# 05.net
KiCad netlist of a schematic drawn in Altium Designer
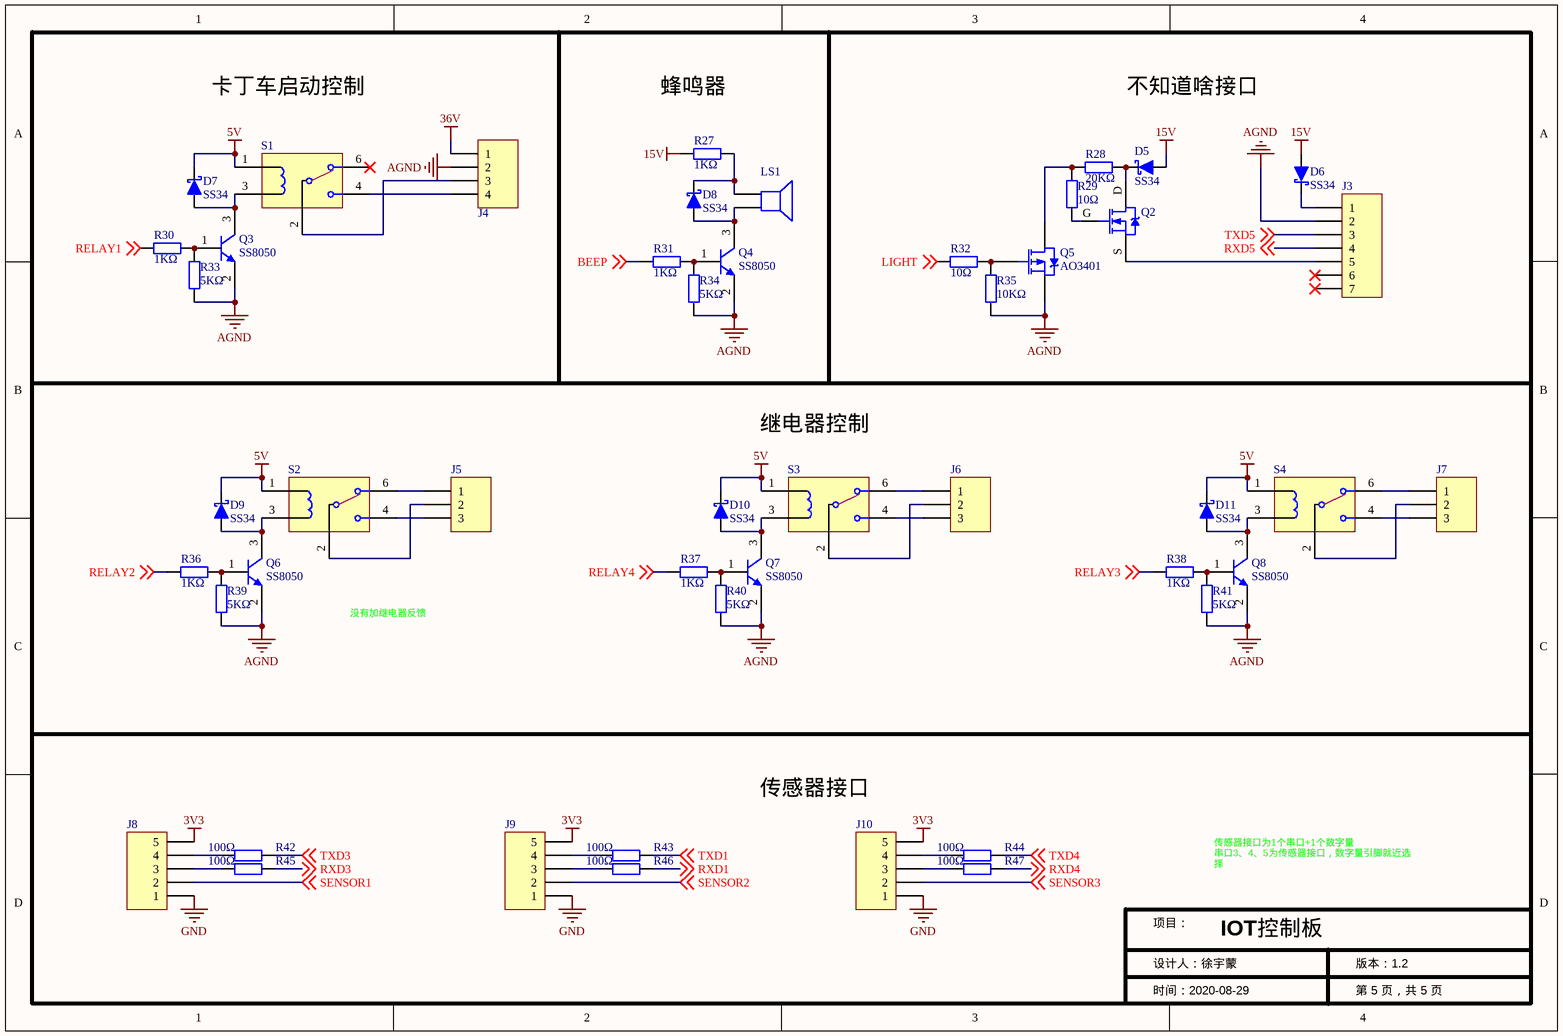
[diagram p0: 05_外部接口与其他部分.SchDoc]

(export (version "E")
  (design (tool "Eeschema 10.0.6"))
  (components
    (comp (ref "D5")
      (value "SS34")
      (footprint "SMA(DO-214AC)")
      (description "Schottky Diode")
      (fields (field (name "PUBLISHER") "Altium Limited"))
      (libsource (lib "元件库") (part "D Schottky"))
    )
    (comp (ref "D6")
      (value "SS34")
      (footprint "SMA(DO-214AC)")
      (description "Schottky Diode")
      (fields (field (name "PUBLISHER") "Altium Limited"))
      (libsource (lib "元件库") (part "D Schottky"))
    )
    (comp (ref "D7")
      (value "SS34")
      (footprint "SMA(DO-214AC)")
      (description "Schottky Diode")
      (fields (field (name "PUBLISHER") "Altium Limited"))
      (libsource (lib "元件库") (part "D Schottky"))
    )
    (comp (ref "D8")
      (value "SS34")
      (footprint "SMA(DO-214AC)")
      (description "Schottky Diode")
      (fields (field (name "PUBLISHER") "Altium Limited"))
      (libsource (lib "元件库") (part "D Schottky"))
    )
    (comp (ref "D9")
      (value "SS34")
      (footprint "SMA(DO-214AC)")
      (description "Schottky Diode")
      (fields (field (name "PUBLISHER") "Altium Limited"))
      (libsource (lib "元件库") (part "D Schottky"))
    )
    (comp (ref "D10")
      (value "SS34")
      (footprint "SMA(DO-214AC)")
      (description "Schottky Diode")
      (fields (field (name "PUBLISHER") "Altium Limited"))
      (libsource (lib "元件库") (part "D Schottky"))
    )
    (comp (ref "D11")
      (value "SS34")
      (footprint "SMA(DO-214AC)")
      (description "Schottky Diode")
      (fields (field (name "PUBLISHER") "Altium Limited"))
      (libsource (lib "元件库") (part "D Schottky"))
    )
    (comp (ref "J3")
      (value "Header7")
      (footprint "Header_7X1_XH_2.54_弯针")
      (description "接插件")
      (libsource (lib "Arrowy_Racing") (part "Header7"))
    )
    (comp (ref "J4")
      (value "Header 4")
      (footprint "Header_4P_XH_2.54_弯脚")
      (description "接插件")
      (fields (field (name "PUBLISHER") "Altium Limited"))
      (libsource (lib "Arrowy_Racing") (part "Header 4"))
    )
    (comp (ref "J5")
      (value "Header3")
      (footprint "Header_3X1_XH_2.54_弯脚")
      (description "接插件")
      (libsource (lib "Arrowy_Racing") (part "Header3"))
    )
    (comp (ref "J6")
      (value "Header3")
      (footprint "Header_3X1_XH_2.54_弯脚")
      (description "接插件")
      (libsource (lib "Arrowy_Racing") (part "Header3"))
    )
    (comp (ref "J7")
      (value "Header3")
      (footprint "Header_3X1_XH_2.54_弯脚")
      (description "接插件")
      (libsource (lib "Arrowy_Racing") (part "Header3"))
    )
    (comp (ref "J8")
      (value "Header5")
      (footprint "Header_5X1_XH_2.54_弯针")
      (description "接插件")
      (libsource (lib "Arrowy_Racing") (part "Header5"))
    )
    (comp (ref "J9")
      (value "Header5")
      (footprint "Header_5X1_XH_2.54_弯针")
      (description "接插件")
      (libsource (lib "Arrowy_Racing") (part "Header5"))
    )
    (comp (ref "J10")
      (value "Header5")
      (footprint "Header_5X1_XH_2.54_弯针")
      (description "接插件")
      (libsource (lib "Arrowy_Racing") (part "Header5"))
    )
    (comp (ref "LS1")
      (value "蜂鸣器")
      (footprint "蜂鸣器 9*5mm")
      (description "Loudspeaker")
      (fields (field (name "PUBLISHER") "Altium Limited"))
      (libsource (lib "Arrowy_Racing") (part "Speaker"))
    )
    (comp (ref "Q2")
      (value "AO3400")
      (footprint "SOT-23-MOSFET")
      (description "N沟道MOS管")
      (libsource (lib "Arrowy_Racing") (part "MOSFET-N"))
    )
    (comp (ref "Q3")
      (value "SS8050")
      (footprint "SOT-23")
      (description "NPN贴片三极管")
      (fields (field (name "PUBLISHER") "Altium Limited"))
      (libsource (lib "Arrowy_Racing") (part "SS8050"))
    )
    (comp (ref "Q4")
      (value "SS8050")
      (footprint "SOT-23")
      (description "NPN贴片三极管")
      (fields (field (name "PUBLISHER") "Altium Limited"))
      (libsource (lib "Arrowy_Racing") (part "SS8050"))
    )
    (comp (ref "Q5")
      (value "AO3401")
      (footprint "SOT-23-MOSFET")
      (description "P沟道MOS管")
      (libsource (lib "Arrowy_Racing") (part "MOSFET-P"))
    )
    (comp (ref "Q6")
      (value "SS8050")
      (footprint "SOT-23")
      (description "NPN贴片三极管")
      (fields (field (name "PUBLISHER") "Altium Limited"))
      (libsource (lib "Arrowy_Racing") (part "SS8050"))
    )
    (comp (ref "Q7")
      (value "SS8050")
      (footprint "SOT-23")
      (description "NPN贴片三极管")
      (fields (field (name "PUBLISHER") "Altium Limited"))
      (libsource (lib "Arrowy_Racing") (part "SS8050"))
    )
    (comp (ref "Q8")
      (value "SS8050")
      (footprint "SOT-23")
      (description "NPN贴片三极管")
      (fields (field (name "PUBLISHER") "Altium Limited"))
      (libsource (lib "Arrowy_Racing") (part "SS8050"))
    )
    (comp (ref "R27")
      (value "1KΩ")
      (footprint "0603")
      (description "贴片电阻")
      (fields (field (name "Comment") "Res") (field (name "PUBLISHER") "Altium Limited"))
      (libsource (lib "Arrowy_Racing") (part "Res"))
    )
    (comp (ref "R28")
      (value "20KΩ")
      (footprint "0603")
      (description "贴片电阻")
      (fields (field (name "Comment") "Res") (field (name "PUBLISHER") "Altium Limited"))
      (libsource (lib "Arrowy_Racing") (part "Res"))
    )
    (comp (ref "R29")
      (value "10Ω")
      (footprint "0603")
      (description "贴片电阻")
      (fields (field (name "Comment") "Res") (field (name "PUBLISHER") "Altium Limited"))
      (libsource (lib "") (part "Res_3"))
    )
    (comp (ref "R30")
      (value "1KΩ")
      (footprint "0603")
      (description "贴片电阻")
      (fields (field (name "Comment") "Res") (field (name "PUBLISHER") "Altium Limited"))
      (libsource (lib "Arrowy_Racing") (part "Res"))
    )
    (comp (ref "R31")
      (value "1KΩ")
      (footprint "0603")
      (description "贴片电阻")
      (fields (field (name "Comment") "Res") (field (name "PUBLISHER") "Altium Limited"))
      (libsource (lib "Arrowy_Racing") (part "Res"))
    )
    (comp (ref "R32")
      (value "10Ω")
      (footprint "0603")
      (description "贴片电阻")
      (fields (field (name "Comment") "Res") (field (name "PUBLISHER") "Altium Limited"))
      (libsource (lib "Arrowy_Racing") (part "Res"))
    )
    (comp (ref "R33")
      (value "5KΩ")
      (footprint "0603")
      (description "贴片电阻")
      (fields (field (name "Comment") "Res") (field (name "PUBLISHER") "Altium Limited"))
      (libsource (lib "") (part "Res_2"))
    )
    (comp (ref "R34")
      (value "5KΩ")
      (footprint "0603")
      (description "贴片电阻")
      (fields (field (name "Comment") "Res") (field (name "PUBLISHER") "Altium Limited"))
      (libsource (lib "") (part "Res_2"))
    )
    (comp (ref "R35")
      (value "10KΩ")
      (footprint "0603")
      (description "贴片电阻")
      (fields (field (name "Comment") "Res") (field (name "PUBLISHER") "Altium Limited"))
      (libsource (lib "") (part "Res_2"))
    )
    (comp (ref "R36")
      (value "1KΩ")
      (footprint "0603")
      (description "贴片电阻")
      (fields (field (name "Comment") "Res") (field (name "PUBLISHER") "Altium Limited"))
      (libsource (lib "Arrowy_Racing") (part "Res"))
    )
    (comp (ref "R37")
      (value "1KΩ")
      (footprint "0603")
      (description "贴片电阻")
      (fields (field (name "Comment") "Res") (field (name "PUBLISHER") "Altium Limited"))
      (libsource (lib "Arrowy_Racing") (part "Res"))
    )
    (comp (ref "R38")
      (value "1KΩ")
      (footprint "0603")
      (description "贴片电阻")
      (fields (field (name "Comment") "Res") (field (name "PUBLISHER") "Altium Limited"))
      (libsource (lib "Arrowy_Racing") (part "Res"))
    )
    (comp (ref "R39")
      (value "5KΩ")
      (footprint "0603")
      (description "贴片电阻")
      (fields (field (name "Comment") "Res") (field (name "PUBLISHER") "Altium Limited"))
      (libsource (lib "") (part "Res_2"))
    )
    (comp (ref "R40")
      (value "5KΩ")
      (footprint "0603")
      (description "贴片电阻")
      (fields (field (name "Comment") "Res") (field (name "PUBLISHER") "Altium Limited"))
      (libsource (lib "") (part "Res_2"))
    )
    (comp (ref "R41")
      (value "5KΩ")
      (footprint "0603")
      (description "贴片电阻")
      (fields (field (name "Comment") "Res") (field (name "PUBLISHER") "Altium Limited"))
      (libsource (lib "") (part "Res_2"))
    )
    (comp (ref "R42")
      (value "100Ω")
      (footprint "0603")
      (description "贴片电阻")
      (fields (field (name "Comment") "Res") (field (name "PUBLISHER") "Altium Limited"))
      (libsource (lib "") (part "Res_1"))
    )
    (comp (ref "R43")
      (value "100Ω")
      (footprint "0603")
      (description "贴片电阻")
      (fields (field (name "Comment") "Res") (field (name "PUBLISHER") "Altium Limited"))
      (libsource (lib "") (part "Res_1"))
    )
    (comp (ref "R44")
      (value "100Ω")
      (footprint "0603")
      (description "贴片电阻")
      (fields (field (name "Comment") "Res") (field (name "PUBLISHER") "Altium Limited"))
      (libsource (lib "") (part "Res_1"))
    )
    (comp (ref "R45")
      (value "100Ω")
      (footprint "0603")
      (description "贴片电阻")
      (fields (field (name "Comment") "Res") (field (name "PUBLISHER") "Altium Limited"))
      (libsource (lib "") (part "Res_1"))
    )
    (comp (ref "R46")
      (value "100Ω")
      (footprint "0603")
      (description "贴片电阻")
      (fields (field (name "Comment") "Res") (field (name "PUBLISHER") "Altium Limited"))
      (libsource (lib "") (part "Res_1"))
    )
    (comp (ref "R47")
      (value "100Ω")
      (footprint "0603")
      (description "贴片电阻")
      (fields (field (name "Comment") "Res") (field (name "PUBLISHER") "Altium Limited"))
      (libsource (lib "") (part "Res_1"))
    )
    (comp (ref "S1")
      (value "Delay")
      (footprint "SongLe_Relay")
      (description "松乐继电器")
      (libsource (lib "Arrowy_Racing") (part "SongLe_Relay"))
    )
    (comp (ref "S2")
      (value "Delay")
      (footprint "SongLe_Relay")
      (description "松乐继电器")
      (libsource (lib "Arrowy_Racing") (part "SongLe_Relay"))
    )
    (comp (ref "S3")
      (value "Delay")
      (footprint "SongLe_Relay")
      (description "松乐继电器")
      (libsource (lib "Arrowy_Racing") (part "SongLe_Relay"))
    )
    (comp (ref "S4")
      (value "Delay")
      (footprint "SongLe_Relay")
      (description "松乐继电器")
      (libsource (lib "Arrowy_Racing") (part "SongLe_Relay"))
    )
  )
  (nets
    (net (code "1") (name "3V3") (class "Default")
      (node (ref "J10") (pin "5") (pinfunction "5_5") (pintype "passive"))
      (node (ref "J8") (pin "5") (pinfunction "5_5") (pintype "passive"))
      (node (ref "J9") (pin "5") (pinfunction "5_5") (pintype "passive"))
    )
    (net (code "2") (name "5V") (class "Default")
      (node (ref "D10") (pin "2") (pinfunction "K_2") (pintype "passive"))
      (node (ref "D11") (pin "2") (pinfunction "K_2") (pintype "passive"))
      (node (ref "D7") (pin "2") (pinfunction "K_2") (pintype "passive"))
      (node (ref "D9") (pin "2") (pinfunction "K_2") (pintype "passive"))
      (node (ref "S1") (pin "1") (pinfunction "1_1") (pintype "passive"))
      (node (ref "S2") (pin "1") (pinfunction "1_1") (pintype "passive"))
      (node (ref "S3") (pin "1") (pinfunction "1_1") (pintype "passive"))
      (node (ref "S4") (pin "1") (pinfunction "1_1") (pintype "passive"))
    )
    (net (code "3") (name "15V") (class "Default")
      (node (ref "D5") (pin "1") (pinfunction "A_1") (pintype "passive"))
      (node (ref "D6") (pin "1") (pinfunction "A_1") (pintype "passive"))
      (node (ref "R27") (pin "2") (pinfunction "2_2") (pintype "passive"))
    )
    (net (code "4") (name "36V") (class "Default")
      (node (ref "J4") (pin "1") (pinfunction "1_1") (pintype "passive"))
    )
    (net (code "5") (name "AGND") (class "Default")
      (node (ref "J3") (pin "2") (pinfunction "2_2") (pintype "passive"))
      (node (ref "J4") (pin "2") (pinfunction "2_2") (pintype "passive"))
      (node (ref "Q3") (pin "2") (pinfunction "E_2") (pintype "passive"))
      (node (ref "Q4") (pin "2") (pinfunction "E_2") (pintype "passive"))
      (node (ref "Q5") (pin "S") (pinfunction "S_S") (pintype "passive"))
      (node (ref "Q6") (pin "2") (pinfunction "E_2") (pintype "passive"))
      (node (ref "Q7") (pin "2") (pinfunction "E_2") (pintype "passive"))
      (node (ref "Q8") (pin "2") (pinfunction "E_2") (pintype "passive"))
      (node (ref "R33") (pin "1") (pinfunction "1_1") (pintype "passive"))
      (node (ref "R34") (pin "1") (pinfunction "1_1") (pintype "passive"))
      (node (ref "R35") (pin "1") (pinfunction "1_1") (pintype "passive"))
      (node (ref "R39") (pin "1") (pinfunction "1_1") (pintype "passive"))
      (node (ref "R40") (pin "1") (pinfunction "1_1") (pintype "passive"))
      (node (ref "R41") (pin "1") (pinfunction "1_1") (pintype "passive"))
    )
    (net (code "6") (name "BEEP") (class "Default")
      (node (ref "R31") (pin "2") (pinfunction "2_2") (pintype "passive"))
    )
    (net (code "7") (name "GND") (class "Default")
      (node (ref "J10") (pin "1") (pinfunction "1_1") (pintype "passive"))
      (node (ref "J8") (pin "1") (pinfunction "1_1") (pintype "passive"))
      (node (ref "J9") (pin "1") (pinfunction "1_1") (pintype "passive"))
    )
    (net (code "8") (name "LIGHT") (class "Default")
      (node (ref "R32") (pin "2") (pinfunction "2_2") (pintype "passive"))
    )
    (net (code "9") (name "Net-(D5-K)") (class "Default")
      (node (ref "D5") (pin "2") (pinfunction "K_2") (pintype "passive"))
      (node (ref "Q2") (pin "D") (pinfunction "D_D") (pintype "passive"))
      (node (ref "R28") (pin "1") (pinfunction "1_1") (pintype "passive"))
    )
    (net (code "10") (name "Net-(D6-K)") (class "Default")
      (node (ref "D6") (pin "2") (pinfunction "K_2") (pintype "passive"))
      (node (ref "J3") (pin "1") (pinfunction "1_1") (pintype "passive"))
    )
    (net (code "11") (name "Net-(D7-A)") (class "Default")
      (node (ref "D7") (pin "1") (pinfunction "A_1") (pintype "passive"))
      (node (ref "Q3") (pin "3") (pinfunction "C_3") (pintype "passive"))
      (node (ref "S1") (pin "3") (pinfunction "3_3") (pintype "passive"))
    )
    (net (code "12") (name "Net-(D8-A)") (class "Default")
      (node (ref "D8") (pin "1") (pinfunction "A_1") (pintype "passive"))
      (node (ref "LS1") (pin "2") (pinfunction "2_2") (pintype "passive"))
      (node (ref "Q4") (pin "3") (pinfunction "C_3") (pintype "passive"))
    )
    (net (code "13") (name "Net-(D8-K)") (class "Default")
      (node (ref "D8") (pin "2") (pinfunction "K_2") (pintype "passive"))
      (node (ref "LS1") (pin "1") (pinfunction "1_1") (pintype "passive"))
      (node (ref "R27") (pin "1") (pinfunction "1_1") (pintype "passive"))
    )
    (net (code "14") (name "Net-(D9-A)") (class "Default")
      (node (ref "D9") (pin "1") (pinfunction "A_1") (pintype "passive"))
      (node (ref "Q6") (pin "3") (pinfunction "C_3") (pintype "passive"))
      (node (ref "S2") (pin "3") (pinfunction "3_3") (pintype "passive"))
    )
    (net (code "15") (name "Net-(D10-A)") (class "Default")
      (node (ref "D10") (pin "1") (pinfunction "A_1") (pintype "passive"))
      (node (ref "Q7") (pin "3") (pinfunction "C_3") (pintype "passive"))
      (node (ref "S3") (pin "3") (pinfunction "3_3") (pintype "passive"))
    )
    (net (code "16") (name "Net-(D11-A)") (class "Default")
      (node (ref "D11") (pin "1") (pinfunction "A_1") (pintype "passive"))
      (node (ref "Q8") (pin "3") (pinfunction "C_3") (pintype "passive"))
      (node (ref "S4") (pin "3") (pinfunction "3_3") (pintype "passive"))
    )
    (net (code "17") (name "Net-(J3-Pad5)") (class "Default")
      (node (ref "J3") (pin "5") (pinfunction "5_5") (pintype "passive"))
      (node (ref "Q2") (pin "S") (pinfunction "S_S") (pintype "passive"))
    )
    (net (code "18") (name "Net-(J4-Pad3)") (class "Default")
      (node (ref "J4") (pin "3") (pinfunction "3_3") (pintype "passive"))
      (node (ref "S1") (pin "2") (pinfunction "2_2") (pintype "passive"))
    )
    (net (code "19") (name "Net-(J4-Pad4)") (class "Default")
      (node (ref "J4") (pin "4") (pinfunction "4_4") (pintype "passive"))
      (node (ref "S1") (pin "4") (pinfunction "4_4") (pintype "passive"))
    )
    (net (code "20") (name "Net-(J5-Pad1)") (class "Default")
      (node (ref "J5") (pin "1") (pinfunction "1_1") (pintype "passive"))
      (node (ref "S2") (pin "6") (pinfunction "6_6") (pintype "passive"))
    )
    (net (code "21") (name "Net-(J5-Pad2)") (class "Default")
      (node (ref "J5") (pin "2") (pinfunction "2_2") (pintype "passive"))
      (node (ref "S2") (pin "2") (pinfunction "2_2") (pintype "passive"))
    )
    (net (code "22") (name "Net-(J5-Pad3)") (class "Default")
      (node (ref "J5") (pin "3") (pinfunction "3_3") (pintype "passive"))
      (node (ref "S2") (pin "4") (pinfunction "4_4") (pintype "passive"))
    )
    (net (code "23") (name "Net-(J6-Pad1)") (class "Default")
      (node (ref "J6") (pin "1") (pinfunction "1_1") (pintype "passive"))
      (node (ref "S3") (pin "6") (pinfunction "6_6") (pintype "passive"))
    )
    (net (code "24") (name "Net-(J6-Pad2)") (class "Default")
      (node (ref "J6") (pin "2") (pinfunction "2_2") (pintype "passive"))
      (node (ref "S3") (pin "2") (pinfunction "2_2") (pintype "passive"))
    )
    (net (code "25") (name "Net-(J6-Pad3)") (class "Default")
      (node (ref "J6") (pin "3") (pinfunction "3_3") (pintype "passive"))
      (node (ref "S3") (pin "4") (pinfunction "4_4") (pintype "passive"))
    )
    (net (code "26") (name "Net-(J7-Pad1)") (class "Default")
      (node (ref "J7") (pin "1") (pinfunction "1_1") (pintype "passive"))
      (node (ref "S4") (pin "6") (pinfunction "6_6") (pintype "passive"))
    )
    (net (code "27") (name "Net-(J7-Pad2)") (class "Default")
      (node (ref "J7") (pin "2") (pinfunction "2_2") (pintype "passive"))
      (node (ref "S4") (pin "2") (pinfunction "2_2") (pintype "passive"))
    )
    (net (code "28") (name "Net-(J7-Pad3)") (class "Default")
      (node (ref "J7") (pin "3") (pinfunction "3_3") (pintype "passive"))
      (node (ref "S4") (pin "4") (pinfunction "4_4") (pintype "passive"))
    )
    (net (code "29") (name "Net-(J8-Pad3)") (class "Default")
      (node (ref "J8") (pin "3") (pinfunction "3_3") (pintype "passive"))
      (node (ref "R45") (pin "1") (pinfunction "1_1") (pintype "passive"))
    )
    (net (code "30") (name "Net-(J8-Pad4)") (class "Default")
      (node (ref "J8") (pin "4") (pinfunction "4_4") (pintype "passive"))
      (node (ref "R42") (pin "1") (pinfunction "1_1") (pintype "passive"))
    )
    (net (code "31") (name "Net-(J9-Pad3)") (class "Default")
      (node (ref "J9") (pin "3") (pinfunction "3_3") (pintype "passive"))
      (node (ref "R46") (pin "1") (pinfunction "1_1") (pintype "passive"))
    )
    (net (code "32") (name "Net-(J9-Pad4)") (class "Default")
      (node (ref "J9") (pin "4") (pinfunction "4_4") (pintype "passive"))
      (node (ref "R43") (pin "1") (pinfunction "1_1") (pintype "passive"))
    )
    (net (code "33") (name "Net-(J10-Pad3)") (class "Default")
      (node (ref "J10") (pin "3") (pinfunction "3_3") (pintype "passive"))
      (node (ref "R47") (pin "1") (pinfunction "1_1") (pintype "passive"))
    )
    (net (code "34") (name "Net-(J10-Pad4)") (class "Default")
      (node (ref "J10") (pin "4") (pinfunction "4_4") (pintype "passive"))
      (node (ref "R44") (pin "1") (pinfunction "1_1") (pintype "passive"))
    )
    (net (code "35") (name "Net-(Q2-PadG)") (class "Default")
      (node (ref "Q2") (pin "G") (pinfunction "G_G") (pintype "passive"))
      (node (ref "R29") (pin "2") (pinfunction "2_2") (pintype "passive"))
    )
    (net (code "36") (name "Net-(Q3-B)") (class "Default")
      (node (ref "Q3") (pin "1") (pinfunction "B_1") (pintype "passive"))
      (node (ref "R30") (pin "1") (pinfunction "1_1") (pintype "passive"))
      (node (ref "R33") (pin "2") (pinfunction "2_2") (pintype "passive"))
    )
    (net (code "37") (name "Net-(Q4-B)") (class "Default")
      (node (ref "Q4") (pin "1") (pinfunction "B_1") (pintype "passive"))
      (node (ref "R31") (pin "1") (pinfunction "1_1") (pintype "passive"))
      (node (ref "R34") (pin "2") (pinfunction "2_2") (pintype "passive"))
    )
    (net (code "38") (name "Net-(Q5-PadD)") (class "Default")
      (node (ref "Q5") (pin "D") (pinfunction "D_D") (pintype "passive"))
      (node (ref "R28") (pin "2") (pinfunction "2_2") (pintype "passive"))
      (node (ref "R29") (pin "1") (pinfunction "1_1") (pintype "passive"))
    )
    (net (code "39") (name "Net-(Q5-PadG)") (class "Default")
      (node (ref "Q5") (pin "G") (pinfunction "G_G") (pintype "passive"))
      (node (ref "R32") (pin "1") (pinfunction "1_1") (pintype "passive"))
      (node (ref "R35") (pin "2") (pinfunction "2_2") (pintype "passive"))
    )
    (net (code "40") (name "Net-(Q6-B)") (class "Default")
      (node (ref "Q6") (pin "1") (pinfunction "B_1") (pintype "passive"))
      (node (ref "R36") (pin "1") (pinfunction "1_1") (pintype "passive"))
      (node (ref "R39") (pin "2") (pinfunction "2_2") (pintype "passive"))
    )
    (net (code "41") (name "Net-(Q7-B)") (class "Default")
      (node (ref "Q7") (pin "1") (pinfunction "B_1") (pintype "passive"))
      (node (ref "R37") (pin "1") (pinfunction "1_1") (pintype "passive"))
      (node (ref "R40") (pin "2") (pinfunction "2_2") (pintype "passive"))
    )
    (net (code "42") (name "Net-(Q8-B)") (class "Default")
      (node (ref "Q8") (pin "1") (pinfunction "B_1") (pintype "passive"))
      (node (ref "R38") (pin "1") (pinfunction "1_1") (pintype "passive"))
      (node (ref "R41") (pin "2") (pinfunction "2_2") (pintype "passive"))
    )
    (net (code "43") (name "RELAY1") (class "Default")
      (node (ref "R30") (pin "2") (pinfunction "2_2") (pintype "passive"))
    )
    (net (code "44") (name "RELAY2") (class "Default")
      (node (ref "R36") (pin "2") (pinfunction "2_2") (pintype "passive"))
    )
    (net (code "45") (name "RELAY3") (class "Default")
      (node (ref "R38") (pin "2") (pinfunction "2_2") (pintype "passive"))
    )
    (net (code "46") (name "RELAY4") (class "Default")
      (node (ref "R37") (pin "2") (pinfunction "2_2") (pintype "passive"))
    )
    (net (code "47") (name "RXD1") (class "Default")
      (node (ref "R46") (pin "2") (pinfunction "2_2") (pintype "passive"))
    )
    (net (code "48") (name "RXD3") (class "Default")
      (node (ref "R45") (pin "2") (pinfunction "2_2") (pintype "passive"))
    )
    (net (code "49") (name "RXD4") (class "Default")
      (node (ref "R47") (pin "2") (pinfunction "2_2") (pintype "passive"))
    )
    (net (code "50") (name "RXD5") (class "Default")
      (node (ref "J3") (pin "4") (pinfunction "4_4") (pintype "passive"))
    )
    (net (code "51") (name "SENSOR1") (class "Default")
      (node (ref "J8") (pin "2") (pinfunction "2_2") (pintype "passive"))
    )
    (net (code "52") (name "SENSOR2") (class "Default")
      (node (ref "J9") (pin "2") (pinfunction "2_2") (pintype "passive"))
    )
    (net (code "53") (name "SENSOR3") (class "Default")
      (node (ref "J10") (pin "2") (pinfunction "2_2") (pintype "passive"))
    )
    (net (code "54") (name "TXD1") (class "Default")
      (node (ref "R43") (pin "2") (pinfunction "2_2") (pintype "passive"))
    )
    (net (code "55") (name "TXD3") (class "Default")
      (node (ref "R42") (pin "2") (pinfunction "2_2") (pintype "passive"))
    )
    (net (code "56") (name "TXD4") (class "Default")
      (node (ref "R44") (pin "2") (pinfunction "2_2") (pintype "passive"))
    )
    (net (code "57") (name "TXD5") (class "Default")
      (node (ref "J3") (pin "3") (pinfunction "3_3") (pintype "passive"))
    )
    (net (code "58") (name "unconnected-(J3-Pad6)") (class "Default")
      (node (ref "J3") (pin "6") (pinfunction "6_6") (pintype "passive+no_connect"))
    )
    (net (code "59") (name "unconnected-(J3-Pad7)") (class "Default")
      (node (ref "J3") (pin "7") (pinfunction "7_7") (pintype "passive+no_connect"))
    )
    (net (code "60") (name "unconnected-(S1-Pad6)") (class "Default")
      (node (ref "S1") (pin "6") (pinfunction "6_6") (pintype "passive+no_connect"))
    )
  )
)
